# fan_control.net
KiCad netlist of a schematic drawn in Altium Designer
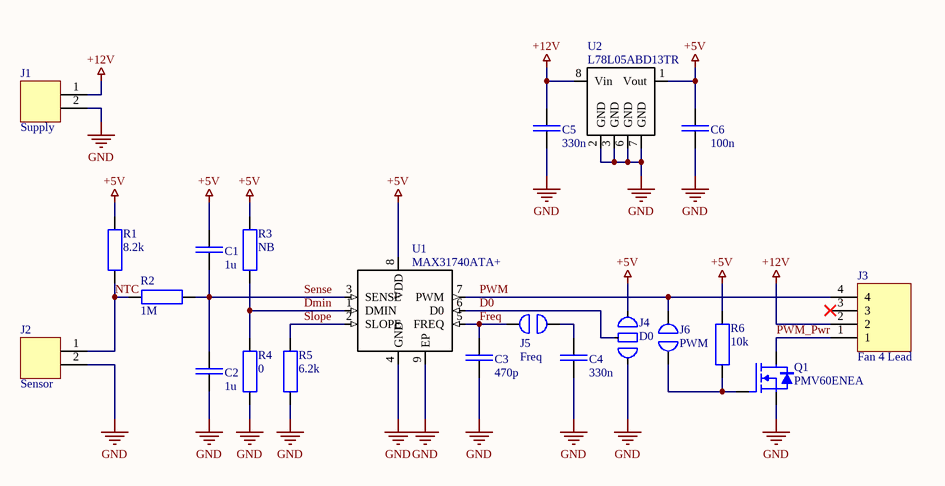
[diagram p0: fan_control.SchDoc]

(export (version "E")
  (design (tool "Eeschema 10.0.6"))
  (components
    (comp (ref "C1")
      (value "1u")
      (footprint "AMZ_Altium_Lib:C_0805_S")
      (libsource (lib "AMZ_Altium_Lib") (part "C"))
    )
    (comp (ref "C2")
      (value "1u")
      (footprint "AMZ_Altium_Lib:C_0805_S")
      (libsource (lib "AMZ_Altium_Lib") (part "C"))
    )
    (comp (ref "C3")
      (value "470p")
      (footprint "AMZ_Altium_Lib:C_0805_S")
      (libsource (lib "AMZ_Altium_Lib") (part "C"))
    )
    (comp (ref "C4")
      (value "330n")
      (footprint "AMZ_Altium_Lib:C_0805_S")
      (libsource (lib "AMZ_Altium_Lib") (part "C"))
    )
    (comp (ref "C5")
      (value "330n")
      (footprint "AMZ_Altium_Lib:C_0805_S")
      (libsource (lib "AMZ_Altium_Lib") (part "C"))
    )
    (comp (ref "C6")
      (value "100n")
      (footprint "AMZ_Altium_Lib:C_0805_S")
      (libsource (lib "AMZ_Altium_Lib") (part "C"))
    )
    (comp (ref "J1")
      (value "Supply")
      (footprint "AMZ_Altium_Lib:HEADER_2_RM_2.54")
      (libsource (lib "AMZ_Altium_Lib") (part "CON2"))
    )
    (comp (ref "J2")
      (value "Sensor")
      (footprint "AMZ_Altium_Lib:HEADER_2_RM_2.54")
      (libsource (lib "AMZ_Altium_Lib") (part "CON2"))
    )
    (comp (ref "J3")
      (value "Fan 4 Lead")
      (footprint "CON_1x4_RM2.5_Molex_MINI_LATCH")
      (libsource (lib "AMZ_Altium_Lib") (part "CON4"))
    )
    (comp (ref "J4")
      (value "D0")
      (footprint "AMZ_Altium_Lib:Solder_Jumper_3pin_0.3mm")
      (libsource (lib "AMZ_Altium_Lib") (part "SolderJumper_3"))
    )
    (comp (ref "J5")
      (value "Freq")
      (footprint "AMZ_Altium_Lib:Solder_Jumper_2pin_0.3mm")
      (libsource (lib "AMZ_Altium_Lib") (part "SolderJumper_2"))
    )
    (comp (ref "J6")
      (value "PWM")
      (footprint "AMZ_Altium_Lib:Solder_Jumper_2pin_0.3mm")
      (libsource (lib "AMZ_Altium_Lib") (part "SolderJumper_2"))
    )
    (comp (ref "Q1")
      (value "PMV60ENEA")
      (footprint "AMZ_Altium_Lib:SOT-23")
      (libsource (lib "AMZ_Altium_Lib") (part "MOSFET N"))
    )
    (comp (ref "R1")
      (value "8.2k")
      (footprint "AMZ_Altium_Lib:R_0805_S")
      (description "Normaler Widerstand")
      (libsource (lib "AMZ_Altium_Lib") (part "R"))
    )
    (comp (ref "R2")
      (value "1M")
      (footprint "AMZ_Altium_Lib:R_0805_S")
      (description "Normaler Widerstand")
      (libsource (lib "AMZ_Altium_Lib") (part "R"))
    )
    (comp (ref "R3")
      (value "NB")
      (footprint "AMZ_Altium_Lib:R_0805_S")
      (description "Normaler Widerstand")
      (libsource (lib "AMZ_Altium_Lib") (part "R"))
    )
    (comp (ref "R4")
      (value "0")
      (footprint "AMZ_Altium_Lib:R_0805_S")
      (description "Normaler Widerstand")
      (libsource (lib "AMZ_Altium_Lib") (part "R"))
    )
    (comp (ref "R5")
      (value "6.2k")
      (footprint "AMZ_Altium_Lib:R_0805_S")
      (description "Normaler Widerstand")
      (libsource (lib "AMZ_Altium_Lib") (part "R"))
    )
    (comp (ref "R6")
      (value "10k")
      (footprint "AMZ_Altium_Lib:R_0805_S")
      (description "Normaler Widerstand")
      (libsource (lib "AMZ_Altium_Lib") (part "R"))
    )
    (comp (ref "U1")
      (value "MAX31740ATA+")
      (footprint "fan_control:TDFN-8 0.5mm")
      (description "Ultra-Simple Fan-Speed Controller")
      (libsource (lib "fan_control") (part "MAX31740ATA+"))
    )
    (comp (ref "U2")
      (value "L78L05ABD13TR")
      (footprint "AMZ_Altium_Lib:SOIC8")
      (description "Positive voltage regulator 5V, SO8")
      (libsource (lib "fan_control") (part "L78L05ABD13TR"))
    )
  )
  (nets
    (net (code "1") (name "+5V") (class "Default")
      (node (ref "C1") (pin "1") (pinfunction "1_1") (pintype "passive"))
      (node (ref "C6") (pin "1") (pinfunction "1_1") (pintype "passive"))
      (node (ref "J4") (pin "1") (pinfunction "1_1") (pintype "passive"))
      (node (ref "R1") (pin "1") (pintype "passive"))
      (node (ref "R3") (pin "2") (pintype "passive"))
      (node (ref "R6") (pin "2") (pintype "passive"))
      (node (ref "U1") (pin "8") (pinfunction "VDD_8") (pintype "power_in"))
      (node (ref "U2") (pin "1") (pinfunction "Vout_1") (pintype "passive"))
    )
    (net (code "2") (name "+12V") (class "Default")
      (node (ref "C5") (pin "1") (pinfunction "1_1") (pintype "passive"))
      (node (ref "J1") (pin "1") (pintype "passive"))
      (node (ref "J3") (pin "2") (pinfunction "2_2") (pintype "passive"))
      (node (ref "U2") (pin "8") (pinfunction "Vin_8") (pintype "passive"))
    )
    (net (code "3") (name "/D0") (class "Default")
      (node (ref "J4") (pin "2") (pinfunction "2_2") (pintype "passive"))
      (node (ref "U1") (pin "6") (pinfunction "D0_6") (pintype "input"))
    )
    (net (code "4") (name "/Dmin") (class "Default")
      (node (ref "R3") (pin "1") (pintype "passive"))
      (node (ref "R4") (pin "2") (pintype "passive"))
      (node (ref "U1") (pin "1") (pinfunction "DMIN_1") (pintype "input"))
    )
    (net (code "5") (name "/Freq") (class "Default")
      (node (ref "C3") (pin "1") (pinfunction "1_1") (pintype "passive"))
      (node (ref "J5") (pin "1") (pinfunction "1_1") (pintype "passive"))
      (node (ref "U1") (pin "5") (pinfunction "FREQ_5") (pintype "input"))
    )
    (net (code "6") (name "/NTC") (class "Default")
      (node (ref "J2") (pin "1") (pintype "passive"))
      (node (ref "R1") (pin "2") (pintype "passive"))
      (node (ref "R2") (pin "1") (pintype "passive"))
    )
    (net (code "7") (name "/PWM") (class "Default")
      (node (ref "J3") (pin "4") (pinfunction "4_4") (pintype "passive"))
      (node (ref "J6") (pin "2") (pinfunction "2_2") (pintype "passive"))
      (node (ref "U1") (pin "7") (pinfunction "PWM_7") (pintype "output"))
    )
    (net (code "8") (name "/PWM_Pwr") (class "Default")
      (node (ref "J3") (pin "1") (pinfunction "1_1") (pintype "passive"))
      (node (ref "Q1") (pin "D") (pinfunction "DRAIN_D") (pintype "passive"))
    )
    (net (code "9") (name "/Sense") (class "Default")
      (node (ref "C1") (pin "2") (pinfunction "2_2") (pintype "passive"))
      (node (ref "C2") (pin "1") (pinfunction "1_1") (pintype "passive"))
      (node (ref "R2") (pin "2") (pintype "passive"))
      (node (ref "U1") (pin "3") (pinfunction "SENSE_3") (pintype "input"))
    )
    (net (code "10") (name "/Slope") (class "Default")
      (node (ref "R5") (pin "2") (pintype "passive"))
      (node (ref "U1") (pin "2") (pinfunction "SLOPE_2") (pintype "input"))
    )
    (net (code "11") (name "GND") (class "Default")
      (node (ref "C2") (pin "2") (pinfunction "2_2") (pintype "passive"))
      (node (ref "C3") (pin "2") (pinfunction "2_2") (pintype "passive"))
      (node (ref "C4") (pin "2") (pinfunction "2_2") (pintype "passive"))
      (node (ref "C5") (pin "2") (pinfunction "2_2") (pintype "passive"))
      (node (ref "C6") (pin "2") (pinfunction "2_2") (pintype "passive"))
      (node (ref "J1") (pin "2") (pintype "passive"))
      (node (ref "J2") (pin "2") (pintype "passive"))
      (node (ref "J4") (pin "3") (pinfunction "3_3") (pintype "passive"))
      (node (ref "Q1") (pin "S") (pinfunction "SOURCE_S") (pintype "passive"))
      (node (ref "R4") (pin "1") (pintype "passive"))
      (node (ref "R5") (pin "1") (pintype "passive"))
      (node (ref "U1") (pin "4") (pinfunction "GND_4") (pintype "power_in"))
      (node (ref "U1") (pin "9") (pinfunction "EP_9") (pintype "passive"))
      (node (ref "U2") (pin "2") (pinfunction "GND_2") (pintype "passive"))
      (node (ref "U2") (pin "3") (pinfunction "GND_3") (pintype "passive"))
      (node (ref "U2") (pin "6") (pinfunction "GND_6") (pintype "passive"))
      (node (ref "U2") (pin "7") (pinfunction "GND_7") (pintype "passive"))
    )
    (net (code "12") (name "Net-(C4-Pad1)") (class "Default")
      (node (ref "C4") (pin "1") (pinfunction "1_1") (pintype "passive"))
      (node (ref "J5") (pin "2") (pinfunction "2_2") (pintype "passive"))
    )
    (net (code "13") (name "Net-(Q1-GATE)") (class "Default")
      (node (ref "J6") (pin "1") (pinfunction "1_1") (pintype "passive"))
      (node (ref "Q1") (pin "G") (pinfunction "GATE_G") (pintype "passive"))
      (node (ref "R6") (pin "1") (pintype "passive"))
    )
    (net (code "14") (name "unconnected-(J3-Pad3)") (class "Default")
      (node (ref "J3") (pin "3") (pinfunction "3_3") (pintype "passive+no_connect"))
    )
  )
)
